# LM2596.net
KiCad netlist of a schematic drawn in Altium Designer
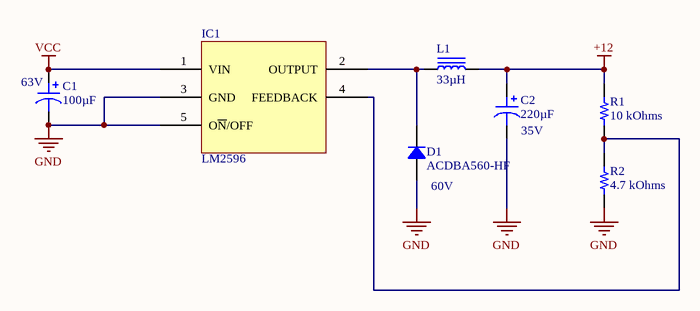
[diagram p0: LM2596.SchDoc]

(export (version "E")
  (design (tool "Eeschema 10.0.6"))
  (components
    (comp (ref "C1")
      (value "100µF")
      (footprint "CAP TH ALUM ELEC D10.00mm S5.00mm H13.50mm")
      (description "CAP ALUM 100UF 20% 63V RADIAL")
      (fields
        (field (name "PART NUMBER") "ECA-1JHG101")
        (field (name "MANUFACTURER") "Panasonic Electronic Components")
        (field (name "VOLTAGE - RATED") "63V")
      )
      (libsource (lib "Celestial Altium Library - altium_library") (part "Polarised Capacitor"))
    )
    (comp (ref "C2")
      (value "220µF")
      (footprint "CAP TH ALUM ELEC D8.00mm S3.50mm H12.50mm")
      (description "CAP ALUM 220UF 20% 35V RADIAL")
      (fields
        (field (name "PART NUMBER") "ECA-1VM221")
        (field (name "MANUFACTURER") "Panasonic Electronic Components")
        (field (name "VOLTAGE - RATED") "35V")
      )
      (libsource (lib "Celestial Altium Library - altium_library") (part "Polarised Capacitor"))
    )
    (comp (ref "D1")
      (value "ACDBA560-HF")
      (footprint "DO214AC SMA")
      (description "DIODE SCHOTTKY 60V 5A DO214AC")
      (fields
        (field (name "MANUFACTURER") "Comchip Technology")
        (field (name "VOLTAGE - FORWARD (VF) (MAX) @ IF") "60V")
      )
      (libsource (lib "Celestial Altium Library - altium_library") (part "Diode"))
    )
    (comp (ref "IC1") (value "LM2596") (footprint "D2PAK") (libsource (lib "lm2596_packet") (part "LM2596")))
    (comp (ref "L1")
      (value "33µH")
      (footprint "BOURNS SRR1280")
      (description "FIXED IND 33UH 3.5A 57 MOHM SMD")
      (fields (field (name "PART NUMBER") "SRR1280-330M") (field (name "MANUFACTURER") "Bourns Inc."))
      (libsource (lib "Celestial Altium Library - altium_library") (part "Inductor"))
    )
    (comp (ref "R1")
      (value "10 kOhms")
      (footprint "RES 0805_2012")
      (description "RES 10K OHM 1% 1/4W 0805")
      (fields
        (field (name "PART NUMBER") "RNCP0805FTD10K0")
        (field (name "MANUFACTURER") "Stackpole Electronics Inc")
      )
      (libsource (lib "Celestial Altium Library - altium_library") (part "Resistor"))
    )
    (comp (ref "R2")
      (value "4.7 kOhms")
      (footprint "RES 0805_2012")
      (description "RES SMD 4.7K OHM 1% 1/8W 0805")
      (fields (field (name "PART NUMBER") "RC0805FR-074K7P") (field (name "MANUFACTURER") "Yageo"))
      (libsource (lib "Celestial Altium Library - altium_library") (part "Resistor"))
    )
  )
  (nets
    (net (code "1") (name "+12") (class "Default")
      (node (ref "C2") (pin "1") (pinfunction "1_1") (pintype "passive"))
      (node (ref "L1") (pin "2") (pinfunction "2_2") (pintype "passive"))
      (node (ref "R1") (pin "2") (pinfunction "2_2") (pintype "passive"))
    )
    (net (code "2") (name "GND") (class "Default")
      (node (ref "C1") (pin "2") (pinfunction "2_2") (pintype "passive"))
      (node (ref "C2") (pin "2") (pinfunction "2_2") (pintype "passive"))
      (node (ref "D1") (pin "1") (pinfunction "1_1") (pintype "passive"))
      (node (ref "IC1") (pin "3") (pinfunction "GND_3") (pintype "passive"))
      (node (ref "IC1") (pin "5") (pinfunction "O~{N}/OFF_5") (pintype "passive"))
      (node (ref "R2") (pin "1") (pinfunction "1_1") (pintype "passive"))
    )
    (net (code "3") (name "Net-(IC1-FEEDBACK)") (class "Default")
      (node (ref "IC1") (pin "4") (pinfunction "FEEDBACK_4") (pintype "passive"))
      (node (ref "R1") (pin "1") (pinfunction "1_1") (pintype "passive"))
      (node (ref "R2") (pin "2") (pinfunction "2_2") (pintype "passive"))
    )
    (net (code "4") (name "Net-(IC1-OUTPUT)") (class "Default")
      (node (ref "D1") (pin "2") (pinfunction "2_2") (pintype "passive"))
      (node (ref "IC1") (pin "2") (pinfunction "OUTPUT_2") (pintype "passive"))
      (node (ref "L1") (pin "1") (pinfunction "1_1") (pintype "passive"))
    )
    (net (code "5") (name "VCC") (class "Default")
      (node (ref "C1") (pin "1") (pinfunction "1_1") (pintype "passive"))
      (node (ref "IC1") (pin "1") (pinfunction "VIN_1") (pintype "passive"))
    )
  )
)
